# Sense_4_Signal_Isolation.net
KiCad netlist of a schematic drawn in Altium Designer
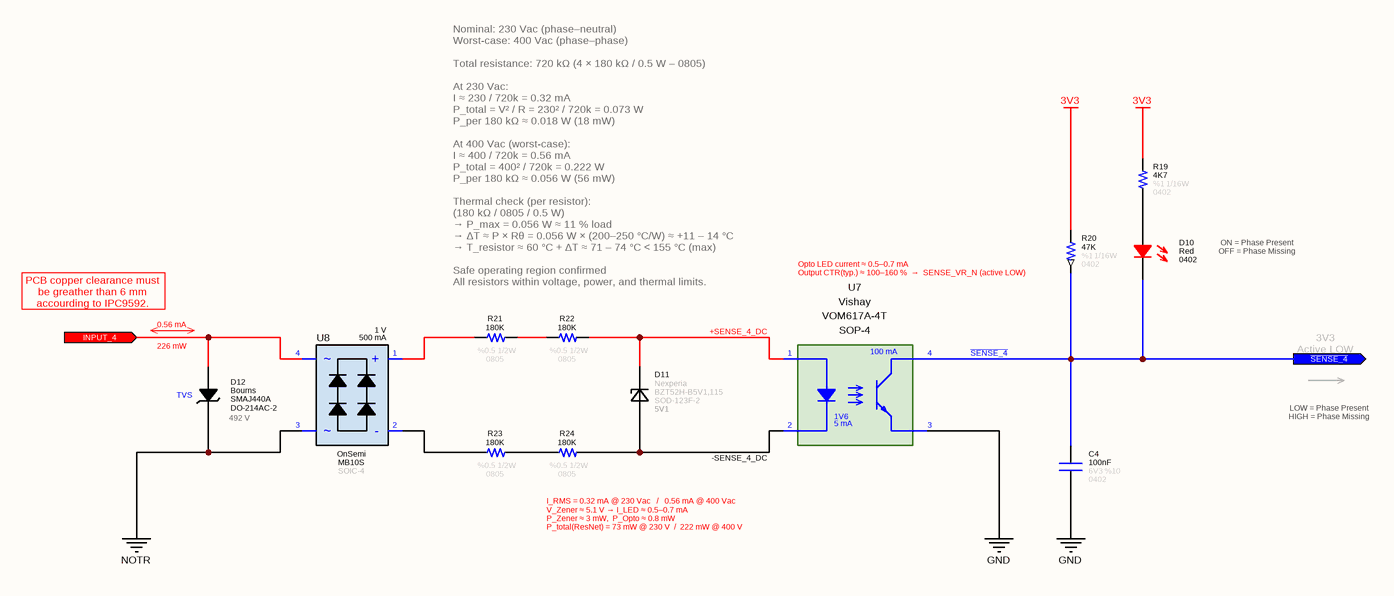
[diagram p0: Sense 4 Signal Isolation.SchDoc]

(export (version "E")
  (design (tool "Eeschema 10.0.6"))
  (components
    (comp (ref "C4")
      (value "100nF")
      (footprint "CAPACITOR_0402")
      (description "Capacitor (MLCC) - 100nF / 6V3 / 0402")
      (fields
        (field (name "MANUFACTURER PART NUMBER") "04026D104KAT4A")
        (field (name "TOLERANCE") "%10")
        (field (name "VOLTAGE") "6V3")
        (field (name "CASE") "0402")
        (field (name "Comment") "Capacitor - 100nF [0402] (MLCC)")
      )
      (libsource (lib "Akkoyun") (part "Capacitor - 100nF [0402-6V3]"))
    )
    (comp (ref "D10")
      (value "SMD LED (Red)")
      (footprint "LED_0402")
      (description "Standard LEDs - SMD MINI-MOLD ULTRA COMPACT RED")
      (fields
        (field (name "MANUFACTURER PART NUMBER") "SML-P12VTT86R")
        (field (name "CASE") "0402")
        (field (name "COLOR") "Red")
      )
      (libsource (lib "Akkoyun") (part "Diode - LED (0402-Red)"))
    )
    (comp (ref "D11")
      (value "BZT52H-B5V1,115")
      (footprint "SOD-123F-2")
      (description "Zener Diodes BZT52H-B5V1/SOD123F/SOD2")
      (fields
        (field (name "ZENER VOLTAGE") "5V1")
        (field (name "MANUFACTURER NAME") "Nexperia")
        (field (name "MANUFACTURER PART NUMBER") "BZT52H-B5V1,115")
        (field (name "CASE") "SOD-123F-2")
      )
      (libsource (lib "Akkoyun") (part "Diode - BZT52H-B5V1,115"))
    )
    (comp (ref "D12")
      (value "SMAJ440A")
      (footprint "DO-220AA-2")
      (description "ESD Protection Diodes / TVS Diodes 440volts 1uA .6 Amps Uni-Dir")
      (fields
        (field (name "BREAKDOWN VOLTAGE") "492 V")
        (field (name "MANUFACTURER NAME") "Bourns")
        (field (name "MANUFACTURER PART NUMBER") "SMAJ440A")
        (field (name "CASE") "DO-214AC-2")
      )
      (libsource (lib "Akkoyun") (part "Diode - SMAJ440A (TVS)"))
    )
    (comp (ref "R19")
      (value "4K7")
      (footprint "RESISTOR_0402")
      (description "Thick Film Resistors - SMD 1/16 W 4.7 KOhm 1%")
      (fields
        (field (name "MANUFACTURER PART NUMBER") "CRCW04024K70FKED")
        (field (name "TOLERANCE") "%1")
        (field (name "CASE") "0402")
        (field (name "POWER") "1/16W")
        (field (name "Comment") "4K7 - 0402 - %1 - 1/16W")
      )
      (libsource (lib "Akkoyun") (part "Resistor - 4K7 [0402]"))
    )
    (comp (ref "R20")
      (value "47K")
      (footprint "RESISTOR_0402")
      (description "Thick Film Resistors - SMD 1/16 W 47 KOhm 1%")
      (fields
        (field (name "MANUFACTURER PART NUMBER") "CRCW040247K0FKED")
        (field (name "TOLERANCE") "%1")
        (field (name "CASE") "0402")
        (field (name "POWER") "1/16W")
        (field (name "Comment") "47K - 0402 - %1 - 1/16W")
      )
      (libsource (lib "Akkoyun") (part "Resistor - 47K [0402]"))
    )
    (comp (ref "R21")
      (value "180K")
      (footprint "RESISTOR_0805")
      (description "Thick Film Resistors - SMD 0805 180Kohms 0.5W 0.5% AEC-Q200")
      (fields
        (field (name "MANUFACTURER PART NUMBER") "ERJ-P06D1803V")
        (field (name "TOLERANCE") "%0.5")
        (field (name "CASE") "0805")
        (field (name "POWER") "1/2W")
        (field (name "Comment") "180K - 0805 - %0.5 - 1/2W")
      )
      (libsource (lib "Akkoyun") (part "Resistor - 180K [0805]"))
    )
    (comp (ref "R22")
      (value "180K")
      (footprint "RESISTOR_0805")
      (description "Thick Film Resistors - SMD 0805 180Kohms 0.5W 0.5% AEC-Q200")
      (fields
        (field (name "MANUFACTURER PART NUMBER") "ERJ-P06D1803V")
        (field (name "TOLERANCE") "%0.5")
        (field (name "CASE") "0805")
        (field (name "POWER") "1/2W")
        (field (name "Comment") "180K - 0805 - %0.5 - 1/2W")
      )
      (libsource (lib "Akkoyun") (part "Resistor - 180K [0805]"))
    )
    (comp (ref "R23")
      (value "180K")
      (footprint "RESISTOR_0805")
      (description "Thick Film Resistors - SMD 0805 180Kohms 0.5W 0.5% AEC-Q200")
      (fields
        (field (name "MANUFACTURER PART NUMBER") "ERJ-P06D1803V")
        (field (name "TOLERANCE") "%0.5")
        (field (name "CASE") "0805")
        (field (name "POWER") "1/2W")
        (field (name "Comment") "180K - 0805 - %0.5 - 1/2W")
      )
      (libsource (lib "Akkoyun") (part "Resistor - 180K [0805]"))
    )
    (comp (ref "R24")
      (value "180K")
      (footprint "RESISTOR_0805")
      (description "Thick Film Resistors - SMD 0805 180Kohms 0.5W 0.5% AEC-Q200")
      (fields
        (field (name "MANUFACTURER PART NUMBER") "ERJ-P06D1803V")
        (field (name "TOLERANCE") "%0.5")
        (field (name "CASE") "0805")
        (field (name "POWER") "1/2W")
        (field (name "Comment") "180K - 0805 - %0.5 - 1/2W")
      )
      (libsource (lib "Akkoyun") (part "Resistor - 180K [0805]"))
    )
    (comp (ref "U7")
      (value "VOM617A-4T")
      (footprint "SOP-4V2")
      (description "Transistor Output Optocouplers Phototransistor Out CTR 160-320% 5mA")
      (fields
        (field (name "MANUFACTURER PART NUMBER") "VOM617A-4T")
        (field (name "MANUFACTURER NAME") "Vishay")
        (field (name "CASE") "SOP-4")
        (field (name "IF - FORWARD CURRENT") "5 mA")
        (field (name "VF - FORWARD VOLTAGE") "1V6")
        (field (name "MAXIMUM COLLECTOR CURRENT") "100 mA")
      )
      (libsource (lib "Akkoyun") (part "IC - VOM617A"))
    )
    (comp (ref "U8")
      (value "LTV-846S")
      (footprint "SOIC-4")
      (description "Transistor Output Optocouplers Optocplr Phototrans 4-Channel")
      (fields
        (field (name "IF - FORWARD CURRENT") "500 mA")
        (field (name "VF - FORWARD VOLTAGE") "1 V")
        (field (name "MANUFACTURER NAME") "OnSemi")
        (field (name "MANUFACTURER PART NUMBER") "MB10S")
        (field (name "CASE") "SOIC-4")
      )
      (libsource (lib "Akkoyun") (part "IC - MB10S"))
    )
  )
  (nets
    (net (code "1") (name "/+SENSE_4_DC") (class "Default")
      (node (ref "D11") (pin "1") (pinfunction "Cathode_1") (pintype "passive"))
      (node (ref "R22") (pin "1") (pinfunction "1_1") (pintype "passive"))
      (node (ref "U7") (pin "1") (pinfunction "LED_Anode_1") (pintype "passive"))
    )
    (net (code "2") (name "/-SENSE_4_DC") (class "Default")
      (node (ref "D11") (pin "2") (pinfunction "Anode_2") (pintype "passive"))
      (node (ref "R24") (pin "1") (pinfunction "1_1") (pintype "passive"))
      (node (ref "U7") (pin "2") (pinfunction "LED_Cathode_2") (pintype "passive"))
    )
    (net (code "3") (name "/INPUT_4") (class "Default")
      (node (ref "D12") (pin "1") (pinfunction "Anode_1") (pintype "passive"))
      (node (ref "U8") (pin "4") (pinfunction "~_4") (pintype "passive"))
    )
    (net (code "4") (name "/~{SENSE_4}") (class "Default")
      (node (ref "C4") (pin "2") (pinfunction "2_2") (pintype "passive"))
      (node (ref "D10") (pin "1") (pinfunction "1_1") (pintype "passive"))
      (node (ref "R20") (pin "1") (pinfunction "1_1") (pintype "output"))
      (node (ref "U7") (pin "4") (pinfunction "Collector_4") (pintype "passive"))
    )
    (net (code "5") (name "3V3") (class "Default")
      (node (ref "R19") (pin "2") (pinfunction "2_2") (pintype "passive"))
      (node (ref "R20") (pin "2") (pinfunction "2_2") (pintype "passive"))
    )
    (net (code "6") (name "GND") (class "Default")
      (node (ref "C4") (pin "1") (pinfunction "1_1") (pintype "passive"))
      (node (ref "U7") (pin "3") (pinfunction "Emiter_3") (pintype "passive"))
    )
    (net (code "7") (name "NOTR") (class "Default")
      (node (ref "D12") (pin "2") (pinfunction "Cathode_2") (pintype "passive"))
      (node (ref "U8") (pin "3") (pinfunction "~_3") (pintype "passive"))
    )
    (net (code "8") (name "Net-(D10-Pad2)") (class "Default")
      (node (ref "D10") (pin "2") (pinfunction "2_2") (pintype "passive"))
      (node (ref "R19") (pin "1") (pinfunction "1_1") (pintype "passive"))
    )
    (net (code "9") (name "Net-(R21-Pad1)") (class "Default")
      (node (ref "R21") (pin "1") (pinfunction "1_1") (pintype "passive"))
      (node (ref "R22") (pin "2") (pinfunction "2_2") (pintype "passive"))
    )
    (net (code "10") (name "Net-(R23-Pad1)") (class "Default")
      (node (ref "R23") (pin "1") (pinfunction "1_1") (pintype "passive"))
      (node (ref "R24") (pin "2") (pinfunction "2_2") (pintype "passive"))
    )
    (net (code "11") (name "Net-(U8-+)") (class "Default")
      (node (ref "R21") (pin "2") (pinfunction "2_2") (pintype "passive"))
      (node (ref "U8") (pin "1") (pinfunction "+_1") (pintype "passive"))
    )
    (net (code "12") (name "Net-(U8--)") (class "Default")
      (node (ref "R23") (pin "2") (pinfunction "2_2") (pintype "passive"))
      (node (ref "U8") (pin "2") (pinfunction "-_2") (pintype "passive"))
    )
  )
)
